# monroe-lo.net
KiCad netlist of a schematic drawn in EAGLE
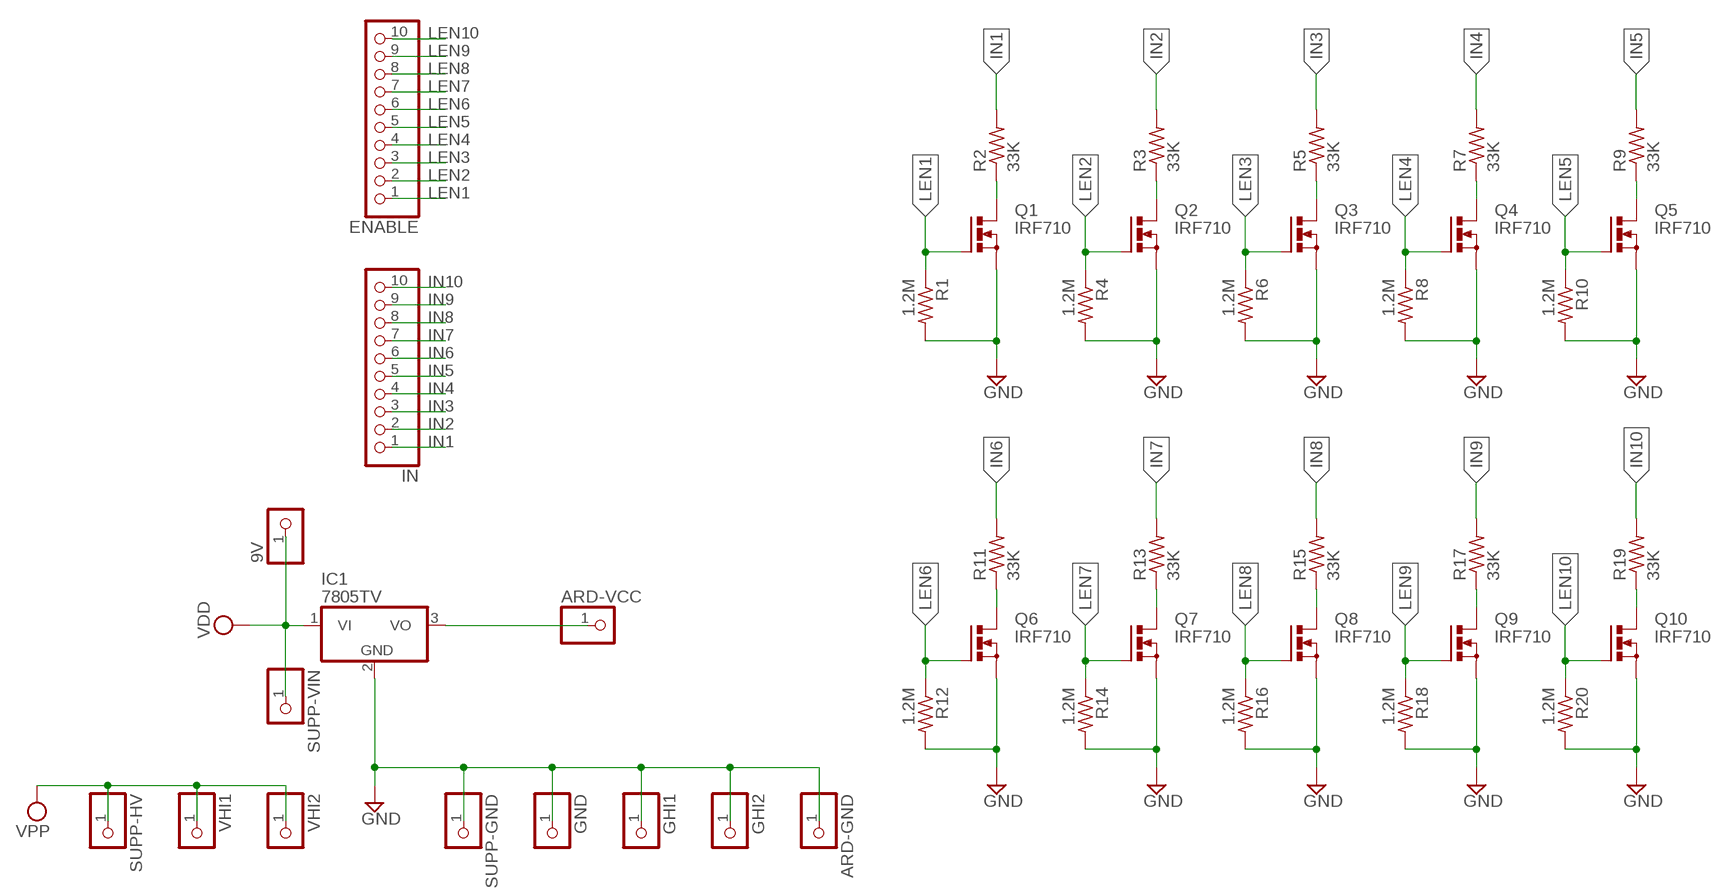
[diagram p0: schematic, sheet 1]

(export (version "E")
  (design (tool "Eeschema 10.0.6"))
  (components
    (comp (ref "9V")
      (value "PINHD-1X1")
      (footprint "eagle-import:1X01")
      (libsource (lib "eagle-import") (part "PINHD-1X1"))
    )
    (comp (ref "ARD-GND")
      (value "PINHD-1X1")
      (footprint "eagle-import:1X01")
      (libsource (lib "eagle-import") (part "PINHD-1X1"))
    )
    (comp (ref "ARD-VCC")
      (value "PINHD-1X1")
      (footprint "eagle-import:1X01")
      (libsource (lib "eagle-import") (part "PINHD-1X1"))
    )
    (comp (ref "ENABLE")
      (value "PINHD-1X10")
      (footprint "eagle-import:1X10")
      (libsource (lib "eagle-import") (part "PINHD-1X10"))
    )
    (comp (ref "GHI1")
      (value "PINHD-1X1")
      (footprint "eagle-import:1X01")
      (libsource (lib "eagle-import") (part "PINHD-1X1"))
    )
    (comp (ref "GHI2")
      (value "PINHD-1X1")
      (footprint "eagle-import:1X01")
      (libsource (lib "eagle-import") (part "PINHD-1X1"))
    )
    (comp (ref "GND")
      (value "PINHD-1X1")
      (footprint "eagle-import:1X01")
      (libsource (lib "eagle-import") (part "PINHD-1X1"))
    )
    (comp (ref "IC1")
      (value "7805TV")
      (footprint "eagle-import:TO220V")
      (libsource (lib "eagle-import") (part "78TV05"))
    )
    (comp (ref "IN")
      (value "PINHD-1X10")
      (footprint "eagle-import:1X10")
      (libsource (lib "eagle-import") (part "PINHD-1X10"))
    )
    (comp (ref "Q1")
      (value "IRF710")
      (footprint "eagle-import:TO220BV")
      (libsource (lib "eagle-import") (part "PMOSFET_NTO220BV"))
    )
    (comp (ref "Q2")
      (value "IRF710")
      (footprint "eagle-import:TO220BV")
      (libsource (lib "eagle-import") (part "PMOSFET_NTO220BV"))
    )
    (comp (ref "Q3")
      (value "IRF710")
      (footprint "eagle-import:TO220BV")
      (libsource (lib "eagle-import") (part "PMOSFET_NTO220BV"))
    )
    (comp (ref "Q4")
      (value "IRF710")
      (footprint "eagle-import:TO220BV")
      (libsource (lib "eagle-import") (part "PMOSFET_NTO220BV"))
    )
    (comp (ref "Q5")
      (value "IRF710")
      (footprint "eagle-import:TO220BV")
      (libsource (lib "eagle-import") (part "PMOSFET_NTO220BV"))
    )
    (comp (ref "Q6")
      (value "IRF710")
      (footprint "eagle-import:TO220BV")
      (libsource (lib "eagle-import") (part "PMOSFET_NTO220BV"))
    )
    (comp (ref "Q7")
      (value "IRF710")
      (footprint "eagle-import:TO220BV")
      (libsource (lib "eagle-import") (part "PMOSFET_NTO220BV"))
    )
    (comp (ref "Q8")
      (value "IRF710")
      (footprint "eagle-import:TO220BV")
      (libsource (lib "eagle-import") (part "PMOSFET_NTO220BV"))
    )
    (comp (ref "Q9")
      (value "IRF710")
      (footprint "eagle-import:TO220BV")
      (libsource (lib "eagle-import") (part "PMOSFET_NTO220BV"))
    )
    (comp (ref "Q10")
      (value "IRF710")
      (footprint "eagle-import:TO220BV")
      (libsource (lib "eagle-import") (part "PMOSFET_NTO220BV"))
    )
    (comp (ref "R1")
      (value "1.2M")
      (footprint "eagle-import:0207_2V")
      (libsource (lib "eagle-import") (part "R-US_0207/2V"))
    )
    (comp (ref "R2")
      (value "33K")
      (footprint "eagle-import:0207_7")
      (libsource (lib "eagle-import") (part "R-US_0207/7"))
    )
    (comp (ref "R3")
      (value "33K")
      (footprint "eagle-import:0207_7")
      (libsource (lib "eagle-import") (part "R-US_0207/7"))
    )
    (comp (ref "R4")
      (value "1.2M")
      (footprint "eagle-import:0207_2V")
      (libsource (lib "eagle-import") (part "R-US_0207/2V"))
    )
    (comp (ref "R5")
      (value "33K")
      (footprint "eagle-import:0207_7")
      (libsource (lib "eagle-import") (part "R-US_0207/7"))
    )
    (comp (ref "R6")
      (value "1.2M")
      (footprint "eagle-import:0207_2V")
      (libsource (lib "eagle-import") (part "R-US_0207/2V"))
    )
    (comp (ref "R7")
      (value "33K")
      (footprint "eagle-import:0207_7")
      (libsource (lib "eagle-import") (part "R-US_0207/7"))
    )
    (comp (ref "R8")
      (value "1.2M")
      (footprint "eagle-import:0207_2V")
      (libsource (lib "eagle-import") (part "R-US_0207/2V"))
    )
    (comp (ref "R9")
      (value "33K")
      (footprint "eagle-import:0207_7")
      (libsource (lib "eagle-import") (part "R-US_0207/7"))
    )
    (comp (ref "R10")
      (value "1.2M")
      (footprint "eagle-import:0207_2V")
      (libsource (lib "eagle-import") (part "R-US_0207/2V"))
    )
    (comp (ref "R11")
      (value "33K")
      (footprint "eagle-import:0207_7")
      (libsource (lib "eagle-import") (part "R-US_0207/7"))
    )
    (comp (ref "R12")
      (value "1.2M")
      (footprint "eagle-import:0207_2V")
      (libsource (lib "eagle-import") (part "R-US_0207/2V"))
    )
    (comp (ref "R13")
      (value "33K")
      (footprint "eagle-import:0207_7")
      (libsource (lib "eagle-import") (part "R-US_0207/7"))
    )
    (comp (ref "R14")
      (value "1.2M")
      (footprint "eagle-import:0207_2V")
      (libsource (lib "eagle-import") (part "R-US_0207/2V"))
    )
    (comp (ref "R15")
      (value "33K")
      (footprint "eagle-import:0207_7")
      (libsource (lib "eagle-import") (part "R-US_0207/7"))
    )
    (comp (ref "R16")
      (value "1.2M")
      (footprint "eagle-import:0207_2V")
      (libsource (lib "eagle-import") (part "R-US_0207/2V"))
    )
    (comp (ref "R17")
      (value "33K")
      (footprint "eagle-import:0207_7")
      (libsource (lib "eagle-import") (part "R-US_0207/7"))
    )
    (comp (ref "R18")
      (value "1.2M")
      (footprint "eagle-import:0207_2V")
      (libsource (lib "eagle-import") (part "R-US_0207/2V"))
    )
    (comp (ref "R19")
      (value "33K")
      (footprint "eagle-import:0207_7")
      (libsource (lib "eagle-import") (part "R-US_0207/7"))
    )
    (comp (ref "R20")
      (value "1.2M")
      (footprint "eagle-import:0207_2V")
      (libsource (lib "eagle-import") (part "R-US_0207/2V"))
    )
    (comp (ref "SUPP-GND")
      (value "PINHD-1X1")
      (footprint "eagle-import:1X01")
      (libsource (lib "eagle-import") (part "PINHD-1X1"))
    )
    (comp (ref "SUPP-HV")
      (value "PINHD-1X1")
      (footprint "eagle-import:1X01")
      (libsource (lib "eagle-import") (part "PINHD-1X1"))
    )
    (comp (ref "SUPP-VIN")
      (value "PINHD-1X1")
      (footprint "eagle-import:1X01")
      (libsource (lib "eagle-import") (part "PINHD-1X1"))
    )
    (comp (ref "VHI1")
      (value "PINHD-1X1")
      (footprint "eagle-import:1X01")
      (libsource (lib "eagle-import") (part "PINHD-1X1"))
    )
    (comp (ref "VHI2")
      (value "PINHD-1X1")
      (footprint "eagle-import:1X01")
      (libsource (lib "eagle-import") (part "PINHD-1X1"))
    )
  )
  (nets
    (net (code "1") (name "GND") (class "Default")
      (node (ref "ARD-GND") (pin "1") (pinfunction "1_1") (pintype "passive"))
      (node (ref "GHI1") (pin "1") (pinfunction "1_1") (pintype "passive"))
      (node (ref "GHI2") (pin "1") (pinfunction "1_1") (pintype "passive"))
      (node (ref "GND") (pin "1") (pinfunction "1_1") (pintype "passive"))
      (node (ref "IC1") (pin "2") (pinfunction "GND_2") (pintype "passive"))
      (node (ref "Q1") (pin "S") (pinfunction "S_S") (pintype "passive"))
      (node (ref "Q10") (pin "S") (pinfunction "S_S") (pintype "passive"))
      (node (ref "Q2") (pin "S") (pinfunction "S_S") (pintype "passive"))
      (node (ref "Q3") (pin "S") (pinfunction "S_S") (pintype "passive"))
      (node (ref "Q4") (pin "S") (pinfunction "S_S") (pintype "passive"))
      (node (ref "Q5") (pin "S") (pinfunction "S_S") (pintype "passive"))
      (node (ref "Q6") (pin "S") (pinfunction "S_S") (pintype "passive"))
      (node (ref "Q7") (pin "S") (pinfunction "S_S") (pintype "passive"))
      (node (ref "Q8") (pin "S") (pinfunction "S_S") (pintype "passive"))
      (node (ref "Q9") (pin "S") (pinfunction "S_S") (pintype "passive"))
      (node (ref "R1") (pin "2") (pinfunction "2_2") (pintype "passive"))
      (node (ref "R10") (pin "2") (pinfunction "2_2") (pintype "passive"))
      (node (ref "R12") (pin "2") (pinfunction "2_2") (pintype "passive"))
      (node (ref "R14") (pin "2") (pinfunction "2_2") (pintype "passive"))
      (node (ref "R16") (pin "2") (pinfunction "2_2") (pintype "passive"))
      (node (ref "R18") (pin "2") (pinfunction "2_2") (pintype "passive"))
      (node (ref "R20") (pin "2") (pinfunction "2_2") (pintype "passive"))
      (node (ref "R4") (pin "2") (pinfunction "2_2") (pintype "passive"))
      (node (ref "R6") (pin "2") (pinfunction "2_2") (pintype "passive"))
      (node (ref "R8") (pin "2") (pinfunction "2_2") (pintype "passive"))
      (node (ref "SUPP-GND") (pin "1") (pinfunction "1_1") (pintype "passive"))
    )
    (net (code "2") (name "IN1") (class "Default")
      (node (ref "IN") (pin "1") (pinfunction "1_1") (pintype "passive"))
      (node (ref "R2") (pin "2") (pinfunction "2_2") (pintype "passive"))
    )
    (net (code "3") (name "IN2") (class "Default")
      (node (ref "IN") (pin "2") (pinfunction "2_2") (pintype "passive"))
      (node (ref "R3") (pin "2") (pinfunction "2_2") (pintype "passive"))
    )
    (net (code "4") (name "IN3") (class "Default")
      (node (ref "IN") (pin "3") (pinfunction "3_3") (pintype "passive"))
      (node (ref "R5") (pin "2") (pinfunction "2_2") (pintype "passive"))
    )
    (net (code "5") (name "IN4") (class "Default")
      (node (ref "IN") (pin "4") (pinfunction "4_4") (pintype "passive"))
      (node (ref "R7") (pin "2") (pinfunction "2_2") (pintype "passive"))
    )
    (net (code "6") (name "IN5") (class "Default")
      (node (ref "IN") (pin "5") (pinfunction "5_5") (pintype "passive"))
      (node (ref "R9") (pin "2") (pinfunction "2_2") (pintype "passive"))
    )
    (net (code "7") (name "IN6") (class "Default")
      (node (ref "IN") (pin "6") (pinfunction "6_6") (pintype "passive"))
      (node (ref "R11") (pin "2") (pinfunction "2_2") (pintype "passive"))
    )
    (net (code "8") (name "IN7") (class "Default")
      (node (ref "IN") (pin "7") (pinfunction "7_7") (pintype "passive"))
      (node (ref "R13") (pin "2") (pinfunction "2_2") (pintype "passive"))
    )
    (net (code "9") (name "IN8") (class "Default")
      (node (ref "IN") (pin "8") (pinfunction "8_8") (pintype "passive"))
      (node (ref "R15") (pin "2") (pinfunction "2_2") (pintype "passive"))
    )
    (net (code "10") (name "IN9") (class "Default")
      (node (ref "IN") (pin "9") (pinfunction "9_9") (pintype "passive"))
      (node (ref "R17") (pin "2") (pinfunction "2_2") (pintype "passive"))
    )
    (net (code "11") (name "IN10") (class "Default")
      (node (ref "IN") (pin "10") (pinfunction "10_10") (pintype "passive"))
      (node (ref "R19") (pin "2") (pinfunction "2_2") (pintype "passive"))
    )
    (net (code "12") (name "LEN1") (class "Default")
      (node (ref "ENABLE") (pin "1") (pinfunction "1_1") (pintype "passive"))
      (node (ref "Q1") (pin "G") (pinfunction "G_G") (pintype "passive"))
      (node (ref "R1") (pin "1") (pinfunction "1_1") (pintype "passive"))
    )
    (net (code "13") (name "LEN2") (class "Default")
      (node (ref "ENABLE") (pin "2") (pinfunction "2_2") (pintype "passive"))
      (node (ref "Q2") (pin "G") (pinfunction "G_G") (pintype "passive"))
      (node (ref "R4") (pin "1") (pinfunction "1_1") (pintype "passive"))
    )
    (net (code "14") (name "LEN3") (class "Default")
      (node (ref "ENABLE") (pin "3") (pinfunction "3_3") (pintype "passive"))
      (node (ref "Q3") (pin "G") (pinfunction "G_G") (pintype "passive"))
      (node (ref "R6") (pin "1") (pinfunction "1_1") (pintype "passive"))
    )
    (net (code "15") (name "LEN4") (class "Default")
      (node (ref "ENABLE") (pin "4") (pinfunction "4_4") (pintype "passive"))
      (node (ref "Q4") (pin "G") (pinfunction "G_G") (pintype "passive"))
      (node (ref "R8") (pin "1") (pinfunction "1_1") (pintype "passive"))
    )
    (net (code "16") (name "LEN5") (class "Default")
      (node (ref "ENABLE") (pin "5") (pinfunction "5_5") (pintype "passive"))
      (node (ref "Q5") (pin "G") (pinfunction "G_G") (pintype "passive"))
      (node (ref "R10") (pin "1") (pinfunction "1_1") (pintype "passive"))
    )
    (net (code "17") (name "LEN6") (class "Default")
      (node (ref "ENABLE") (pin "6") (pinfunction "6_6") (pintype "passive"))
      (node (ref "Q6") (pin "G") (pinfunction "G_G") (pintype "passive"))
      (node (ref "R12") (pin "1") (pinfunction "1_1") (pintype "passive"))
    )
    (net (code "18") (name "LEN7") (class "Default")
      (node (ref "ENABLE") (pin "7") (pinfunction "7_7") (pintype "passive"))
      (node (ref "Q7") (pin "G") (pinfunction "G_G") (pintype "passive"))
      (node (ref "R14") (pin "1") (pinfunction "1_1") (pintype "passive"))
    )
    (net (code "19") (name "LEN8") (class "Default")
      (node (ref "ENABLE") (pin "8") (pinfunction "8_8") (pintype "passive"))
      (node (ref "Q8") (pin "G") (pinfunction "G_G") (pintype "passive"))
      (node (ref "R16") (pin "1") (pinfunction "1_1") (pintype "passive"))
    )
    (net (code "20") (name "LEN9") (class "Default")
      (node (ref "ENABLE") (pin "9") (pinfunction "9_9") (pintype "passive"))
      (node (ref "Q9") (pin "G") (pinfunction "G_G") (pintype "passive"))
      (node (ref "R18") (pin "1") (pinfunction "1_1") (pintype "passive"))
    )
    (net (code "21") (name "LEN10") (class "Default")
      (node (ref "ENABLE") (pin "10") (pinfunction "10_10") (pintype "passive"))
      (node (ref "Q10") (pin "G") (pinfunction "G_G") (pintype "passive"))
      (node (ref "R20") (pin "1") (pinfunction "1_1") (pintype "passive"))
    )
    (net (code "22") (name "Net-(IC1-VO)") (class "Default")
      (node (ref "ARD-VCC") (pin "1") (pinfunction "1_1") (pintype "passive"))
      (node (ref "IC1") (pin "3") (pinfunction "VO_3") (pintype "passive"))
    )
    (net (code "23") (name "Net-(Q1-PadD)") (class "Default")
      (node (ref "Q1") (pin "D") (pinfunction "D_D") (pintype "passive"))
      (node (ref "R2") (pin "1") (pinfunction "1_1") (pintype "passive"))
    )
    (net (code "24") (name "Net-(Q2-PadD)") (class "Default")
      (node (ref "Q2") (pin "D") (pinfunction "D_D") (pintype "passive"))
      (node (ref "R3") (pin "1") (pinfunction "1_1") (pintype "passive"))
    )
    (net (code "25") (name "Net-(Q3-PadD)") (class "Default")
      (node (ref "Q3") (pin "D") (pinfunction "D_D") (pintype "passive"))
      (node (ref "R5") (pin "1") (pinfunction "1_1") (pintype "passive"))
    )
    (net (code "26") (name "Net-(Q4-PadD)") (class "Default")
      (node (ref "Q4") (pin "D") (pinfunction "D_D") (pintype "passive"))
      (node (ref "R7") (pin "1") (pinfunction "1_1") (pintype "passive"))
    )
    (net (code "27") (name "Net-(Q5-PadD)") (class "Default")
      (node (ref "Q5") (pin "D") (pinfunction "D_D") (pintype "passive"))
      (node (ref "R9") (pin "1") (pinfunction "1_1") (pintype "passive"))
    )
    (net (code "28") (name "Net-(Q6-PadD)") (class "Default")
      (node (ref "Q6") (pin "D") (pinfunction "D_D") (pintype "passive"))
      (node (ref "R11") (pin "1") (pinfunction "1_1") (pintype "passive"))
    )
    (net (code "29") (name "Net-(Q7-PadD)") (class "Default")
      (node (ref "Q7") (pin "D") (pinfunction "D_D") (pintype "passive"))
      (node (ref "R13") (pin "1") (pinfunction "1_1") (pintype "passive"))
    )
    (net (code "30") (name "Net-(Q8-PadD)") (class "Default")
      (node (ref "Q8") (pin "D") (pinfunction "D_D") (pintype "passive"))
      (node (ref "R15") (pin "1") (pinfunction "1_1") (pintype "passive"))
    )
    (net (code "31") (name "Net-(Q9-PadD)") (class "Default")
      (node (ref "Q9") (pin "D") (pinfunction "D_D") (pintype "passive"))
      (node (ref "R17") (pin "1") (pinfunction "1_1") (pintype "passive"))
    )
    (net (code "32") (name "Net-(Q10-PadD)") (class "Default")
      (node (ref "Q10") (pin "D") (pinfunction "D_D") (pintype "passive"))
      (node (ref "R19") (pin "1") (pinfunction "1_1") (pintype "passive"))
    )
    (net (code "33") (name "VDD") (class "Default")
      (node (ref "9V") (pin "1") (pinfunction "1_1") (pintype "passive"))
      (node (ref "IC1") (pin "1") (pinfunction "VI_1") (pintype "input"))
      (node (ref "SUPP-VIN") (pin "1") (pinfunction "1_1") (pintype "passive"))
    )
    (net (code "34") (name "VPP") (class "Default")
      (node (ref "SUPP-HV") (pin "1") (pinfunction "1_1") (pintype "passive"))
      (node (ref "VHI1") (pin "1") (pinfunction "1_1") (pintype "passive"))
      (node (ref "VHI2") (pin "1") (pinfunction "1_1") (pintype "passive"))
    )
  )
)
